# led.net
KiCad netlist of a schematic drawn in EAGLE
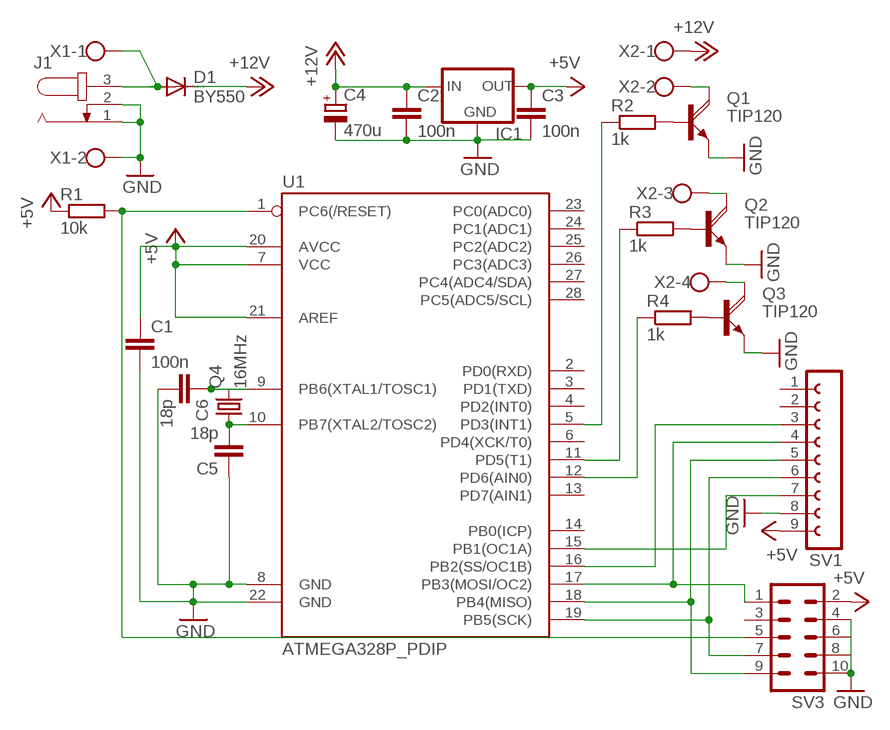
[diagram p0: schematic, sheet 1]

(export (version "E")
  (design (tool "Eeschema 10.0.6"))
  (components
    (comp (ref "C1")
      (value "100n")
      (footprint "eagle-import:C050-024X044")
      (libsource (lib "eagle-import") (part "C-EU050-024X044"))
    )
    (comp (ref "C2")
      (value "100n")
      (footprint "eagle-import:C050-024X044")
      (libsource (lib "eagle-import") (part "C-EU050-024X044"))
    )
    (comp (ref "C3")
      (value "100n")
      (footprint "eagle-import:C050-024X044")
      (libsource (lib "eagle-import") (part "C-EU050-024X044"))
    )
    (comp (ref "C4")
      (value "470u")
      (footprint "eagle-import:E5-10,5")
      (libsource (lib "eagle-import") (part "CPOL-EUE5-10.5"))
    )
    (comp (ref "C5")
      (value "18p")
      (footprint "eagle-import:C050-024X044")
      (libsource (lib "eagle-import") (part "C-EU050-024X044"))
    )
    (comp (ref "C6")
      (value "18p")
      (footprint "eagle-import:C050-024X044")
      (libsource (lib "eagle-import") (part "C-EU050-024X044"))
    )
    (comp (ref "D1")
      (value "BY550")
      (footprint "eagle-import:DO27-15")
      (libsource (lib "eagle-import") (part "BY550"))
    )
    (comp (ref "IC1")
      (value "78XXS")
      (footprint "eagle-import:78XXS")
      (libsource (lib "eagle-import") (part "78XXS"))
    )
    (comp (ref "J1")
      (value "JACK-PLUG1")
      (footprint "eagle-import:SPC4078")
      (libsource (lib "eagle-import") (part "JACK-PLUG1"))
    )
    (comp (ref "Q1")
      (value "TIP120")
      (footprint "eagle-import:TO220AV")
      (libsource (lib "eagle-import") (part "TIP120"))
    )
    (comp (ref "Q2")
      (value "TIP120")
      (footprint "eagle-import:TO220AV")
      (libsource (lib "eagle-import") (part "TIP120"))
    )
    (comp (ref "Q3")
      (value "TIP120")
      (footprint "eagle-import:TO220AV")
      (libsource (lib "eagle-import") (part "TIP120"))
    )
    (comp (ref "Q4")
      (value "16MHz")
      (footprint "eagle-import:HC49_S")
      (libsource (lib "eagle-import") (part "CRYSTALHC49S"))
    )
    (comp (ref "R1")
      (value "10k")
      (footprint "eagle-import:0207_10")
      (libsource (lib "eagle-import") (part "resistor_R-EU_0207/10"))
    )
    (comp (ref "R2")
      (value "1k")
      (footprint "eagle-import:0207_10")
      (libsource (lib "eagle-import") (part "R-EU_0207/10"))
    )
    (comp (ref "R3")
      (value "1k")
      (footprint "eagle-import:0207_10")
      (libsource (lib "eagle-import") (part "R-EU_0207/10"))
    )
    (comp (ref "R4")
      (value "1k")
      (footprint "eagle-import:0207_10")
      (libsource (lib "eagle-import") (part "R-EU_0207/10"))
    )
    (comp (ref "SV1")
      (value "FE09-1")
      (footprint "eagle-import:FE09")
      (libsource (lib "eagle-import") (part "FE09-1"))
    )
    (comp (ref "SV3")
      (value "MA05-2")
      (footprint "eagle-import:MA05-2")
      (libsource (lib "eagle-import") (part "MA05-2"))
    )
    (comp (ref "U1")
      (value "ATMEGA328P_PDIP")
      (footprint "eagle-import:DIL28-3")
      (libsource (lib "eagle-import") (part "ATMEGA328P_PDIP"))
    )
    (comp (ref "X1")
      (value "W237-102")
      (footprint "eagle-import:W237-102")
      (fields (field (name "MPN") "237-102"))
      (libsource (lib "eagle-import") (part "W237-102"))
    )
    (comp (ref "X2")
      (value "W237-4")
      (footprint "eagle-import:W237-4")
      (libsource (lib "eagle-import") (part "W237-4"))
    )
  )
  (nets
    (net (code "1") (name "+5V") (class "Default")
      (node (ref "C1") (pin "1") (pinfunction "1_1") (pintype "passive"))
      (node (ref "C3") (pin "1") (pinfunction "1_1") (pintype "passive"))
      (node (ref "IC1") (pin "OUT") (pinfunction "OUT_OUT") (pintype "passive"))
      (node (ref "R1") (pin "1") (pinfunction "1_1") (pintype "passive"))
      (node (ref "SV1") (pin "9") (pinfunction "9_9") (pintype "passive"))
      (node (ref "SV3") (pin "2") (pinfunction "2_2") (pintype "passive"))
      (node (ref "U1") (pin "20") (pinfunction "AVCC_20") (pintype "bidirectional"))
      (node (ref "U1") (pin "21") (pinfunction "AREF_21") (pintype "bidirectional"))
      (node (ref "U1") (pin "7") (pinfunction "VCC_7") (pintype "bidirectional"))
    )
    (net (code "2") (name "+12V") (class "Default")
      (node (ref "C2") (pin "1") (pinfunction "1_1") (pintype "passive"))
      (node (ref "C4") (pin "+") (pinfunction "+_+") (pintype "passive"))
      (node (ref "D1") (pin "C") (pinfunction "C_C") (pintype "passive"))
      (node (ref "IC1") (pin "IN") (pinfunction "IN_IN") (pintype "input"))
      (node (ref "X2") (pin "1") (pinfunction "KL_1") (pintype "passive"))
    )
    (net (code "3") (name "GND") (class "Default")
      (node (ref "C1") (pin "2") (pinfunction "2_2") (pintype "passive"))
      (node (ref "C2") (pin "2") (pinfunction "2_2") (pintype "passive"))
      (node (ref "C3") (pin "2") (pinfunction "2_2") (pintype "passive"))
      (node (ref "C4") (pin "-") (pinfunction "-_-") (pintype "passive"))
      (node (ref "C5") (pin "1") (pinfunction "1_1") (pintype "passive"))
      (node (ref "C6") (pin "2") (pinfunction "2_2") (pintype "passive"))
      (node (ref "IC1") (pin "GND") (pinfunction "GND_GND") (pintype "input"))
      (node (ref "J1") (pin "1") (pinfunction "1_1") (pintype "passive"))
      (node (ref "J1") (pin "2") (pinfunction "2_2") (pintype "passive"))
      (node (ref "Q1") (pin "E") (pinfunction "E_E") (pintype "passive"))
      (node (ref "Q2") (pin "E") (pinfunction "E_E") (pintype "passive"))
      (node (ref "Q3") (pin "E") (pinfunction "E_E") (pintype "passive"))
      (node (ref "SV1") (pin "8") (pinfunction "8_8") (pintype "passive"))
      (node (ref "SV3") (pin "10") (pinfunction "10_10") (pintype "passive"))
      (node (ref "SV3") (pin "4") (pinfunction "4_4") (pintype "passive"))
      (node (ref "U1") (pin "22") (pinfunction "GND_22") (pintype "bidirectional"))
      (node (ref "U1") (pin "8") (pinfunction "GND_8") (pintype "bidirectional"))
      (node (ref "X1") (pin "2") (pinfunction "KL_2") (pintype "passive"))
    )
    (net (code "4") (name "Net-(Q1-PadB)") (class "Default")
      (node (ref "Q1") (pin "B") (pinfunction "B_B") (pintype "passive"))
      (node (ref "R2") (pin "2") (pinfunction "2_2") (pintype "passive"))
    )
    (net (code "5") (name "Net-(Q2-PadB)") (class "Default")
      (node (ref "Q2") (pin "B") (pinfunction "B_B") (pintype "passive"))
      (node (ref "R3") (pin "2") (pinfunction "2_2") (pintype "passive"))
    )
    (net (code "6") (name "Net-(Q3-PadB)") (class "Default")
      (node (ref "Q3") (pin "B") (pinfunction "B_B") (pintype "passive"))
      (node (ref "R4") (pin "2") (pinfunction "2_2") (pintype "passive"))
    )
    (net (code "7") (name "Net-(U1-PB1(OC1A))") (class "Default")
      (node (ref "SV1") (pin "7") (pinfunction "7_7") (pintype "passive"))
      (node (ref "U1") (pin "15") (pinfunction "PB1(OC1A)_15") (pintype "bidirectional"))
    )
    (net (code "8") (name "Net-(U1-PB2(SS{slash}OC1B))") (class "Default")
      (node (ref "SV1") (pin "3") (pinfunction "3_3") (pintype "passive"))
      (node (ref "U1") (pin "16") (pinfunction "PB2(SS/OC1B)_16") (pintype "bidirectional"))
    )
    (net (code "9") (name "Net-(U1-PB3(MOSI{slash}OC2))") (class "Default")
      (node (ref "SV1") (pin "4") (pinfunction "4_4") (pintype "passive"))
      (node (ref "SV3") (pin "1") (pinfunction "1_1") (pintype "passive"))
      (node (ref "U1") (pin "17") (pinfunction "PB3(MOSI/OC2)_17") (pintype "bidirectional"))
    )
    (net (code "10") (name "Net-(U1-PB4(MISO))") (class "Default")
      (node (ref "SV1") (pin "5") (pinfunction "5_5") (pintype "passive"))
      (node (ref "SV3") (pin "9") (pinfunction "9_9") (pintype "passive"))
      (node (ref "U1") (pin "18") (pinfunction "PB4(MISO)_18") (pintype "bidirectional"))
    )
    (net (code "11") (name "Net-(U1-PB5(SCK))") (class "Default")
      (node (ref "SV1") (pin "6") (pinfunction "6_6") (pintype "passive"))
      (node (ref "SV3") (pin "7") (pinfunction "7_7") (pintype "passive"))
      (node (ref "U1") (pin "19") (pinfunction "PB5(SCK)_19") (pintype "bidirectional"))
    )
    (net (code "12") (name "Net-(U1-PB6(XTAL1{slash}TOSC1))") (class "Default")
      (node (ref "C6") (pin "1") (pinfunction "1_1") (pintype "passive"))
      (node (ref "Q4") (pin "2") (pinfunction "2_2") (pintype "passive"))
      (node (ref "U1") (pin "9") (pinfunction "PB6(XTAL1/TOSC1)_9") (pintype "bidirectional"))
    )
    (net (code "13") (name "Net-(U1-PB7(XTAL2{slash}TOSC2))") (class "Default")
      (node (ref "C5") (pin "2") (pinfunction "2_2") (pintype "passive"))
      (node (ref "Q4") (pin "1") (pinfunction "1_1") (pintype "passive"))
      (node (ref "U1") (pin "10") (pinfunction "PB7(XTAL2/TOSC2)_10") (pintype "bidirectional"))
    )
    (net (code "14") (name "Net-(U1-PC6({slash}RESET))") (class "Default")
      (node (ref "R1") (pin "2") (pinfunction "2_2") (pintype "passive"))
      (node (ref "SV3") (pin "5") (pinfunction "5_5") (pintype "passive"))
      (node (ref "U1") (pin "1") (pinfunction "PC6(/RESET)_1") (pintype "bidirectional"))
    )
    (net (code "15") (name "Net-(U1-PD3(INT1))") (class "Default")
      (node (ref "R2") (pin "1") (pinfunction "1_1") (pintype "passive"))
      (node (ref "U1") (pin "5") (pinfunction "PD3(INT1)_5") (pintype "bidirectional"))
    )
    (net (code "16") (name "Net-(U1-PD5(T1))") (class "Default")
      (node (ref "R3") (pin "1") (pinfunction "1_1") (pintype "passive"))
      (node (ref "U1") (pin "11") (pinfunction "PD5(T1)_11") (pintype "bidirectional"))
    )
    (net (code "17") (name "Net-(U1-PD6(AIN0))") (class "Default")
      (node (ref "R4") (pin "1") (pinfunction "1_1") (pintype "passive"))
      (node (ref "U1") (pin "12") (pinfunction "PD6(AIN0)_12") (pintype "bidirectional"))
    )
    (net (code "18") (name "Net-(X1A-KL)") (class "Default")
      (node (ref "D1") (pin "A") (pinfunction "A_A") (pintype "passive"))
      (node (ref "J1") (pin "3") (pinfunction "3_3") (pintype "passive"))
      (node (ref "X1") (pin "1") (pinfunction "KL_1") (pintype "passive"))
    )
    (net (code "19") (name "Net-(X2B-KL)") (class "Default")
      (node (ref "Q1") (pin "C") (pinfunction "C_C") (pintype "passive"))
      (node (ref "X2") (pin "2") (pinfunction "KL_2") (pintype "passive"))
    )
    (net (code "20") (name "Net-(X2C-KL)") (class "Default")
      (node (ref "Q2") (pin "C") (pinfunction "C_C") (pintype "passive"))
      (node (ref "X2") (pin "3") (pinfunction "KL_3") (pintype "passive"))
    )
    (net (code "21") (name "Net-(X2D-KL)") (class "Default")
      (node (ref "Q3") (pin "C") (pinfunction "C_C") (pintype "passive"))
      (node (ref "X2") (pin "4") (pinfunction "KL_4") (pintype "passive"))
    )
    (net (code "22") (name "unconnected-(SV1-Pad1)") (class "Default")
      (node (ref "SV1") (pin "1") (pinfunction "1_1") (pintype "passive"))
    )
    (net (code "23") (name "unconnected-(SV1-Pad2)") (class "Default")
      (node (ref "SV1") (pin "2") (pinfunction "2_2") (pintype "passive"))
    )
    (net (code "24") (name "unconnected-(SV3-Pad3)") (class "Default")
      (node (ref "SV3") (pin "3") (pinfunction "3_3") (pintype "passive"))
    )
    (net (code "25") (name "unconnected-(SV3-Pad6)") (class "Default")
      (node (ref "SV3") (pin "6") (pinfunction "6_6") (pintype "passive"))
    )
    (net (code "26") (name "unconnected-(SV3-Pad8)") (class "Default")
      (node (ref "SV3") (pin "8") (pinfunction "8_8") (pintype "passive"))
    )
    (net (code "27") (name "unconnected-(U1-PB0(ICP)-Pad14)") (class "Default")
      (node (ref "U1") (pin "14") (pinfunction "PB0(ICP)_14") (pintype "bidirectional"))
    )
    (net (code "28") (name "unconnected-(U1-PC0(ADC0)-Pad23)") (class "Default")
      (node (ref "U1") (pin "23") (pinfunction "PC0(ADC0)_23") (pintype "bidirectional"))
    )
    (net (code "29") (name "unconnected-(U1-PC1(ADC1)-Pad24)") (class "Default")
      (node (ref "U1") (pin "24") (pinfunction "PC1(ADC1)_24") (pintype "bidirectional"))
    )
    (net (code "30") (name "unconnected-(U1-PC2(ADC2)-Pad25)") (class "Default")
      (node (ref "U1") (pin "25") (pinfunction "PC2(ADC2)_25") (pintype "bidirectional"))
    )
    (net (code "31") (name "unconnected-(U1-PC3(ADC3)-Pad26)") (class "Default")
      (node (ref "U1") (pin "26") (pinfunction "PC3(ADC3)_26") (pintype "bidirectional"))
    )
    (net (code "32") (name "unconnected-(U1-PC4(ADC4{slash}SDA)-Pad27)") (class "Default")
      (node (ref "U1") (pin "27") (pinfunction "PC4(ADC4/SDA)_27") (pintype "bidirectional"))
    )
    (net (code "33") (name "unconnected-(U1-PC5(ADC5{slash}SCL)-Pad28)") (class "Default")
      (node (ref "U1") (pin "28") (pinfunction "PC5(ADC5/SCL)_28") (pintype "bidirectional"))
    )
    (net (code "34") (name "unconnected-(U1-PD0(RXD)-Pad2)") (class "Default")
      (node (ref "U1") (pin "2") (pinfunction "PD0(RXD)_2") (pintype "bidirectional"))
    )
    (net (code "35") (name "unconnected-(U1-PD1(TXD)-Pad3)") (class "Default")
      (node (ref "U1") (pin "3") (pinfunction "PD1(TXD)_3") (pintype "bidirectional"))
    )
    (net (code "36") (name "unconnected-(U1-PD2(INT0)-Pad4)") (class "Default")
      (node (ref "U1") (pin "4") (pinfunction "PD2(INT0)_4") (pintype "bidirectional"))
    )
    (net (code "37") (name "unconnected-(U1-PD4(XCK{slash}T0)-Pad6)") (class "Default")
      (node (ref "U1") (pin "6") (pinfunction "PD4(XCK/T0)_6") (pintype "bidirectional"))
    )
    (net (code "38") (name "unconnected-(U1-PD7(AIN1)-Pad13)") (class "Default")
      (node (ref "U1") (pin "13") (pinfunction "PD7(AIN1)_13") (pintype "bidirectional"))
    )
  )
)
